# Sheet1.net
KiCad netlist of a schematic drawn in Altium Designer
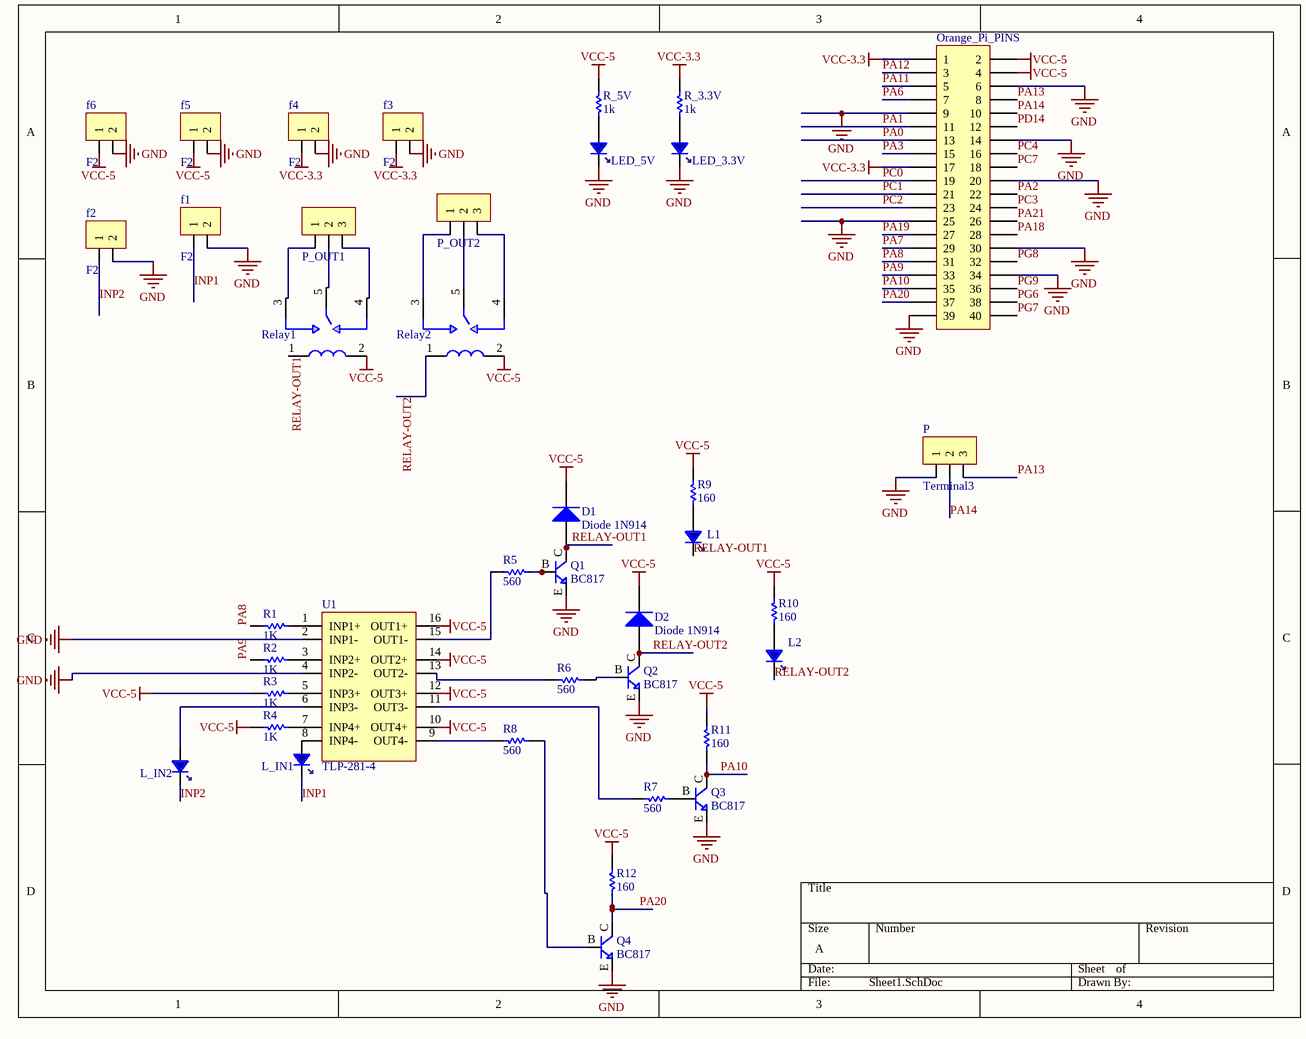
[diagram p0: Sheet1.SchDoc]

(export (version "E")
  (design (tool "Eeschema 10.0.6"))
  (components
    (comp (ref "D1")
      (value "Diode 1N914")
      (footprint "DO-35")
      (description "High Conductance Fast Diode")
      (fields (field (name "PUBLISHER") "Altium Limited"))
      (libsource (lib "Miscellaneous Devices") (part "Diode 1N914"))
    )
    (comp (ref "D2")
      (value "Diode 1N914")
      (footprint "DO-35")
      (description "High Conductance Fast Diode")
      (fields (field (name "PUBLISHER") "Altium Limited"))
      (libsource (lib "Miscellaneous Devices") (part "Diode 1N914"))
    )
    (comp (ref "f1")
      (value "F2")
      (footprint "Fonex(X2):PCBComponent_1")
      (libsource (lib "Fonex(X2)") (part "Component_1"))
    )
    (comp (ref "f2")
      (value "F2")
      (footprint "Fonex(X2):PCBComponent_1")
      (libsource (lib "Fonex(X2)") (part "Component_1"))
    )
    (comp (ref "f3")
      (value "F2")
      (footprint "Fonex(X2):PCBComponent_1")
      (libsource (lib "Fonex(X2)") (part "Component_1"))
    )
    (comp (ref "f4")
      (value "F2")
      (footprint "Fonex(X2):PCBComponent_1")
      (libsource (lib "Fonex(X2)") (part "Component_1"))
    )
    (comp (ref "f5")
      (value "F2")
      (footprint "Fonex(X2):PCBComponent_1")
      (libsource (lib "Fonex(X2)") (part "Component_1"))
    )
    (comp (ref "f6")
      (value "F2")
      (footprint "Fonex(X2):PCBComponent_1")
      (libsource (lib "Fonex(X2)") (part "Component_1"))
    )
    (comp (ref "L1")
      (value "LED_0805")
      (footprint "LED_0805")
      (libsource (lib "Main Board") (part "LED_0805"))
    )
    (comp (ref "L2")
      (value "LED_0805")
      (footprint "LED_0805")
      (libsource (lib "Main Board") (part "LED_0805"))
    )
    (comp (ref "LED_3.3V")
      (value "LED_0805")
      (footprint "LED_0805")
      (libsource (lib "Main Board") (part "LED_0805"))
    )
    (comp (ref "LED_5V")
      (value "LED_0805")
      (footprint "LED_0805")
      (libsource (lib "Main Board") (part "LED_0805"))
    )
    (comp (ref "L_IN1")
      (value "LED_0805")
      (footprint "LED_0805")
      (libsource (lib "Main Board") (part "LED_0805"))
    )
    (comp (ref "L_IN2")
      (value "LED_0805")
      (footprint "LED_0805")
      (libsource (lib "Main Board") (part "LED_0805"))
    )
    (comp (ref "Orange_Pi_PINS")
      (value "Header 20X2")
      (footprint "HDR2X20")
      (description "Header, 20-Pin, Dual row")
      (fields (field (name "PUBLISHER") "Altium Limited"))
      (libsource (lib "Miscellaneous Connectors") (part "Header 20X2"))
    )
    (comp (ref "P")
      (value "Terminal3")
      (footprint "TERMINAL-3")
      (libsource (lib "Lib_Interface") (part "Terminal-3"))
    )
    (comp (ref "P_OUT1")
      (value "Terminal3")
      (footprint "TERMINAL-3")
      (libsource (lib "Lib_Interface") (part "Terminal-3"))
    )
    (comp (ref "P_OUT2")
      (value "Terminal3")
      (footprint "TERMINAL-3")
      (libsource (lib "Lib_Interface") (part "Terminal-3"))
    )
    (comp (ref "Q1")
      (value "BC817")
      (footprint "PCBComponent_1 - duplicate2")
      (libsource (lib "Lib_Interface") (part "Transistor_SMD_NPN"))
    )
    (comp (ref "Q2")
      (value "BC817")
      (footprint "PCBComponent_1 - duplicate2")
      (libsource (lib "Lib_Interface") (part "Transistor_SMD_NPN"))
    )
    (comp (ref "Q3")
      (value "BC817")
      (footprint "PCBComponent_1 - duplicate2")
      (libsource (lib "Lib_Interface") (part "Transistor_SMD_NPN"))
    )
    (comp (ref "Q4")
      (value "BC817")
      (footprint "PCBComponent_1 - duplicate2")
      (libsource (lib "Lib_Interface") (part "Transistor_SMD_NPN"))
    )
    (comp (ref "R1")
      (value "1K")
      (footprint "ResS")
      (fields (field (name "Comment") "Res_0805"))
      (libsource (lib "Main Board") (part "Res_0805"))
    )
    (comp (ref "R2")
      (value "1K")
      (footprint "ResS")
      (fields (field (name "Comment") "Res_0805"))
      (libsource (lib "Main Board") (part "Res_0805"))
    )
    (comp (ref "R3")
      (value "1K")
      (footprint "ResS")
      (fields (field (name "Comment") "Res_0805"))
      (libsource (lib "Main Board") (part "Res_0805"))
    )
    (comp (ref "R4")
      (value "1K")
      (footprint "ResS")
      (fields (field (name "Comment") "Res_0805"))
      (libsource (lib "Main Board") (part "Res_0805"))
    )
    (comp (ref "R5")
      (value "560")
      (footprint "ResS")
      (fields (field (name "Comment") "Res_0805"))
      (libsource (lib "Main Board") (part "Res_0805"))
    )
    (comp (ref "R6")
      (value "560")
      (footprint "ResS")
      (fields (field (name "Comment") "Res_0805"))
      (libsource (lib "Main Board") (part "Res_0805"))
    )
    (comp (ref "R7")
      (value "560")
      (footprint "ResS")
      (fields (field (name "Comment") "Res_0805"))
      (libsource (lib "Main Board") (part "Res_0805"))
    )
    (comp (ref "R8")
      (value "560")
      (footprint "ResS")
      (fields (field (name "Comment") "Res_0805"))
      (libsource (lib "Main Board") (part "Res_0805"))
    )
    (comp (ref "R9")
      (value "160")
      (footprint "ResS")
      (fields (field (name "Comment") "Res_0805"))
      (libsource (lib "Main Board") (part "Res_0805"))
    )
    (comp (ref "R10")
      (value "160")
      (footprint "ResS")
      (fields (field (name "Comment") "Res_0805"))
      (libsource (lib "Main Board") (part "Res_0805"))
    )
    (comp (ref "R11")
      (value "160")
      (footprint "ResS")
      (fields (field (name "Comment") "Res_0805"))
      (libsource (lib "Main Board") (part "Res_0805"))
    )
    (comp (ref "R12")
      (value "160")
      (footprint "ResS")
      (fields (field (name "Comment") "Res_0805"))
      (libsource (lib "Main Board") (part "Res_0805"))
    )
    (comp (ref "Relay1")
      (value "JOC-3FF")
      (footprint "Interface-PCB-Lib:PCBComponent_1")
      (description "Relay")
      (libsource (lib "Lib_Interface") (part "Relay-5VDC"))
    )
    (comp (ref "Relay2")
      (value "JOC-3FF")
      (footprint "Interface-PCB-Lib:PCBComponent_1")
      (description "Relay")
      (libsource (lib "Lib_Interface") (part "Relay-5VDC"))
    )
    (comp (ref "R_3.3V")
      (value "1k")
      (footprint "ResS")
      (fields (field (name "Comment") "Res_0805"))
      (libsource (lib "Main Board") (part "Res_0805"))
    )
    (comp (ref "R_5V")
      (value "1k")
      (footprint "ResS")
      (fields (field (name "Comment") "Res_0805"))
      (libsource (lib "Main Board") (part "Res_0805"))
    )
    (comp (ref "U1")
      (value "TLP-281-4")
      (footprint "TLP281-4")
      (libsource (lib "Lib_Interface") (part "OPTO-TLP281-4"))
    )
  )
  (nets
    (net (code "1") (name "/INP1") (class "Default")
      (node (ref "L_IN1") (pin "2") (pinfunction "CATHODE_2") (pintype "passive"))
      (node (ref "f1") (pin "1") (pinfunction "1_1") (pintype "passive"))
    )
    (net (code "2") (name "/INP2") (class "Default")
      (node (ref "L_IN2") (pin "2") (pinfunction "CATHODE_2") (pintype "passive"))
      (node (ref "f2") (pin "1") (pinfunction "1_1") (pintype "passive"))
    )
    (net (code "3") (name "/PA0") (class "Default")
      (node (ref "Orange_Pi_PINS") (pin "13") (pinfunction "13_13") (pintype "passive"))
    )
    (net (code "4") (name "/PA1") (class "Default")
      (node (ref "Orange_Pi_PINS") (pin "11") (pinfunction "11_11") (pintype "passive"))
    )
    (net (code "5") (name "/PA2") (class "Default")
      (node (ref "Orange_Pi_PINS") (pin "22") (pinfunction "22_22") (pintype "passive"))
    )
    (net (code "6") (name "/PA3") (class "Default")
      (node (ref "Orange_Pi_PINS") (pin "15") (pinfunction "15_15") (pintype "passive"))
    )
    (net (code "7") (name "/PA6") (class "Default")
      (node (ref "Orange_Pi_PINS") (pin "7") (pinfunction "7_7") (pintype "passive"))
    )
    (net (code "8") (name "/PA7") (class "Default")
      (node (ref "Orange_Pi_PINS") (pin "29") (pinfunction "29_29") (pintype "passive"))
    )
    (net (code "9") (name "/PA8") (class "Default")
      (node (ref "Orange_Pi_PINS") (pin "31") (pinfunction "31_31") (pintype "passive"))
      (node (ref "R1") (pin "2") (pinfunction "2_2") (pintype "passive"))
    )
    (net (code "10") (name "/PA9") (class "Default")
      (node (ref "Orange_Pi_PINS") (pin "33") (pinfunction "33_33") (pintype "passive"))
      (node (ref "R2") (pin "1") (pinfunction "1_1") (pintype "passive"))
    )
    (net (code "11") (name "/PA10") (class "Default")
      (node (ref "Orange_Pi_PINS") (pin "35") (pinfunction "35_35") (pintype "passive"))
      (node (ref "Q3") (pin "C") (pinfunction "C_C") (pintype "passive"))
      (node (ref "R11") (pin "1") (pinfunction "1_1") (pintype "passive"))
    )
    (net (code "12") (name "/PA11") (class "Default")
      (node (ref "Orange_Pi_PINS") (pin "5") (pinfunction "5_5") (pintype "passive"))
    )
    (net (code "13") (name "/PA12") (class "Default")
      (node (ref "Orange_Pi_PINS") (pin "3") (pinfunction "3_3") (pintype "passive"))
    )
    (net (code "14") (name "/PA13") (class "Default")
      (node (ref "Orange_Pi_PINS") (pin "8") (pinfunction "8_8") (pintype "passive"))
      (node (ref "P") (pin "3") (pinfunction "3_3") (pintype "passive"))
    )
    (net (code "15") (name "/PA14") (class "Default")
      (node (ref "Orange_Pi_PINS") (pin "10") (pinfunction "10_10") (pintype "passive"))
      (node (ref "P") (pin "2") (pinfunction "2_2") (pintype "passive"))
    )
    (net (code "16") (name "/PA18") (class "Default")
      (node (ref "Orange_Pi_PINS") (pin "28") (pinfunction "28_28") (pintype "passive"))
    )
    (net (code "17") (name "/PA19") (class "Default")
      (node (ref "Orange_Pi_PINS") (pin "27") (pinfunction "27_27") (pintype "passive"))
    )
    (net (code "18") (name "/PA20") (class "Default")
      (node (ref "Orange_Pi_PINS") (pin "37") (pinfunction "37_37") (pintype "passive"))
      (node (ref "Q4") (pin "C") (pinfunction "C_C") (pintype "passive"))
      (node (ref "R12") (pin "1") (pinfunction "1_1") (pintype "passive"))
    )
    (net (code "19") (name "/PA21") (class "Default")
      (node (ref "Orange_Pi_PINS") (pin "26") (pinfunction "26_26") (pintype "passive"))
    )
    (net (code "20") (name "/PC0") (class "Default")
      (node (ref "Orange_Pi_PINS") (pin "19") (pinfunction "19_19") (pintype "passive"))
    )
    (net (code "21") (name "/PC1") (class "Default")
      (node (ref "Orange_Pi_PINS") (pin "21") (pinfunction "21_21") (pintype "passive"))
    )
    (net (code "22") (name "/PC2") (class "Default")
      (node (ref "Orange_Pi_PINS") (pin "23") (pinfunction "23_23") (pintype "passive"))
    )
    (net (code "23") (name "/PC3") (class "Default")
      (node (ref "Orange_Pi_PINS") (pin "24") (pinfunction "24_24") (pintype "passive"))
    )
    (net (code "24") (name "/PC4") (class "Default")
      (node (ref "Orange_Pi_PINS") (pin "16") (pinfunction "16_16") (pintype "passive"))
    )
    (net (code "25") (name "/PC7") (class "Default")
      (node (ref "Orange_Pi_PINS") (pin "18") (pinfunction "18_18") (pintype "passive"))
    )
    (net (code "26") (name "/PD14") (class "Default")
      (node (ref "Orange_Pi_PINS") (pin "12") (pinfunction "12_12") (pintype "passive"))
    )
    (net (code "27") (name "/PG6") (class "Default")
      (node (ref "Orange_Pi_PINS") (pin "38") (pinfunction "38_38") (pintype "passive"))
    )
    (net (code "28") (name "/PG7") (class "Default")
      (node (ref "Orange_Pi_PINS") (pin "40") (pinfunction "40_40") (pintype "passive"))
    )
    (net (code "29") (name "/PG8") (class "Default")
      (node (ref "Orange_Pi_PINS") (pin "32") (pinfunction "32_32") (pintype "passive"))
    )
    (net (code "30") (name "/PG9") (class "Default")
      (node (ref "Orange_Pi_PINS") (pin "36") (pinfunction "36_36") (pintype "passive"))
    )
    (net (code "31") (name "/RELAY-OUT1") (class "Default")
      (node (ref "D1") (pin "1") (pinfunction "A_1") (pintype "passive"))
      (node (ref "L1") (pin "2") (pinfunction "CATHODE_2") (pintype "passive"))
      (node (ref "Q1") (pin "C") (pinfunction "C_C") (pintype "passive"))
      (node (ref "Relay1") (pin "1") (pinfunction "1_1") (pintype "passive"))
    )
    (net (code "32") (name "/RELAY-OUT2") (class "Default")
      (node (ref "D2") (pin "1") (pinfunction "A_1") (pintype "passive"))
      (node (ref "L2") (pin "2") (pinfunction "CATHODE_2") (pintype "passive"))
      (node (ref "Q2") (pin "C") (pinfunction "C_C") (pintype "passive"))
      (node (ref "Relay2") (pin "1") (pinfunction "1_1") (pintype "passive"))
    )
    (net (code "33") (name "GND") (class "Default")
      (node (ref "LED_3.3V") (pin "2") (pinfunction "CATHODE_2") (pintype "passive"))
      (node (ref "LED_5V") (pin "2") (pinfunction "CATHODE_2") (pintype "passive"))
      (node (ref "Orange_Pi_PINS") (pin "14") (pinfunction "14_14") (pintype "passive"))
      (node (ref "Orange_Pi_PINS") (pin "20") (pinfunction "20_20") (pintype "passive"))
      (node (ref "Orange_Pi_PINS") (pin "25") (pinfunction "25_25") (pintype "passive"))
      (node (ref "Orange_Pi_PINS") (pin "30") (pinfunction "30_30") (pintype "passive"))
      (node (ref "Orange_Pi_PINS") (pin "34") (pinfunction "34_34") (pintype "passive"))
      (node (ref "Orange_Pi_PINS") (pin "39") (pinfunction "39_39") (pintype "passive"))
      (node (ref "Orange_Pi_PINS") (pin "6") (pinfunction "6_6") (pintype "passive"))
      (node (ref "Orange_Pi_PINS") (pin "9") (pinfunction "9_9") (pintype "passive"))
      (node (ref "P") (pin "1") (pinfunction "1_1") (pintype "passive"))
      (node (ref "Q1") (pin "E") (pinfunction "E_E") (pintype "passive"))
      (node (ref "Q2") (pin "E") (pinfunction "E_E") (pintype "passive"))
      (node (ref "Q3") (pin "E") (pinfunction "E_E") (pintype "passive"))
      (node (ref "Q4") (pin "E") (pinfunction "E_E") (pintype "passive"))
      (node (ref "U1") (pin "2") (pinfunction "INP1-_2") (pintype "passive"))
      (node (ref "U1") (pin "4") (pinfunction "INP2-_4") (pintype "passive"))
      (node (ref "f1") (pin "2") (pinfunction "2_2") (pintype "passive"))
      (node (ref "f2") (pin "2") (pinfunction "2_2") (pintype "passive"))
      (node (ref "f3") (pin "2") (pinfunction "2_2") (pintype "passive"))
      (node (ref "f4") (pin "2") (pinfunction "2_2") (pintype "passive"))
      (node (ref "f5") (pin "2") (pinfunction "2_2") (pintype "passive"))
      (node (ref "f6") (pin "2") (pinfunction "2_2") (pintype "passive"))
    )
    (net (code "34") (name "Net-(L1-ANODE)") (class "Default")
      (node (ref "L1") (pin "1") (pinfunction "ANODE_1") (pintype "passive"))
      (node (ref "R9") (pin "1") (pinfunction "1_1") (pintype "passive"))
    )
    (net (code "35") (name "Net-(L2-ANODE)") (class "Default")
      (node (ref "L2") (pin "1") (pinfunction "ANODE_1") (pintype "passive"))
      (node (ref "R10") (pin "1") (pinfunction "1_1") (pintype "passive"))
    )
    (net (code "36") (name "Net-(LED_3.3V-ANODE)") (class "Default")
      (node (ref "LED_3.3V") (pin "1") (pinfunction "ANODE_1") (pintype "passive"))
      (node (ref "R_3.3V") (pin "2") (pinfunction "2_2") (pintype "passive"))
    )
    (net (code "37") (name "Net-(LED_5V-ANODE)") (class "Default")
      (node (ref "LED_5V") (pin "1") (pinfunction "ANODE_1") (pintype "passive"))
      (node (ref "R_5V") (pin "1") (pinfunction "1_1") (pintype "passive"))
    )
    (net (code "38") (name "Net-(L_IN1-ANODE)") (class "Default")
      (node (ref "L_IN1") (pin "1") (pinfunction "ANODE_1") (pintype "passive"))
      (node (ref "U1") (pin "8") (pinfunction "INP4-_8") (pintype "passive"))
    )
    (net (code "39") (name "Net-(L_IN2-ANODE)") (class "Default")
      (node (ref "L_IN2") (pin "1") (pinfunction "ANODE_1") (pintype "passive"))
      (node (ref "U1") (pin "6") (pinfunction "INP3-_6") (pintype "passive"))
    )
    (net (code "40") (name "Net-(P_OUT1-Pad1)") (class "Default")
      (node (ref "P_OUT1") (pin "1") (pinfunction "1_1") (pintype "passive"))
      (node (ref "Relay1") (pin "3") (pinfunction "3_3") (pintype "passive"))
    )
    (net (code "41") (name "Net-(P_OUT1-Pad2)") (class "Default")
      (node (ref "P_OUT1") (pin "2") (pinfunction "2_2") (pintype "passive"))
      (node (ref "Relay1") (pin "5") (pinfunction "5_5") (pintype "passive"))
    )
    (net (code "42") (name "Net-(P_OUT1-Pad3)") (class "Default")
      (node (ref "P_OUT1") (pin "3") (pinfunction "3_3") (pintype "passive"))
      (node (ref "Relay1") (pin "4") (pinfunction "4_4") (pintype "passive"))
    )
    (net (code "43") (name "Net-(P_OUT2-Pad1)") (class "Default")
      (node (ref "P_OUT2") (pin "1") (pinfunction "1_1") (pintype "passive"))
      (node (ref "Relay2") (pin "3") (pinfunction "3_3") (pintype "passive"))
    )
    (net (code "44") (name "Net-(P_OUT2-Pad2)") (class "Default")
      (node (ref "P_OUT2") (pin "2") (pinfunction "2_2") (pintype "passive"))
      (node (ref "Relay2") (pin "5") (pinfunction "5_5") (pintype "passive"))
    )
    (net (code "45") (name "Net-(P_OUT2-Pad3)") (class "Default")
      (node (ref "P_OUT2") (pin "3") (pinfunction "3_3") (pintype "passive"))
      (node (ref "Relay2") (pin "4") (pinfunction "4_4") (pintype "passive"))
    )
    (net (code "46") (name "Net-(Q1-PadB)") (class "Default")
      (node (ref "Q1") (pin "B") (pinfunction "B_B") (pintype "passive"))
      (node (ref "R5") (pin "2") (pinfunction "2_2") (pintype "passive"))
    )
    (net (code "47") (name "Net-(Q2-PadB)") (class "Default")
      (node (ref "Q2") (pin "B") (pinfunction "B_B") (pintype "passive"))
      (node (ref "R6") (pin "2") (pinfunction "2_2") (pintype "passive"))
    )
    (net (code "48") (name "Net-(Q3-PadB)") (class "Default")
      (node (ref "Q3") (pin "B") (pinfunction "B_B") (pintype "passive"))
      (node (ref "R7") (pin "2") (pinfunction "2_2") (pintype "passive"))
    )
    (net (code "49") (name "Net-(Q4-PadB)") (class "Default")
      (node (ref "Q4") (pin "B") (pinfunction "B_B") (pintype "passive"))
      (node (ref "R8") (pin "2") (pinfunction "2_2") (pintype "passive"))
    )
    (net (code "50") (name "Net-(U1-INP1+)") (class "Default")
      (node (ref "R1") (pin "1") (pinfunction "1_1") (pintype "passive"))
      (node (ref "U1") (pin "1") (pinfunction "INP1+_1") (pintype "passive"))
    )
    (net (code "51") (name "Net-(U1-INP2+)") (class "Default")
      (node (ref "R2") (pin "2") (pinfunction "2_2") (pintype "passive"))
      (node (ref "U1") (pin "3") (pinfunction "INP2+_3") (pintype "passive"))
    )
    (net (code "52") (name "Net-(U1-INP3+)") (class "Default")
      (node (ref "R3") (pin "2") (pinfunction "2_2") (pintype "passive"))
      (node (ref "U1") (pin "5") (pinfunction "INP3+_5") (pintype "passive"))
    )
    (net (code "53") (name "Net-(U1-INP4+)") (class "Default")
      (node (ref "R4") (pin "2") (pinfunction "2_2") (pintype "passive"))
      (node (ref "U1") (pin "7") (pinfunction "INP4+_7") (pintype "passive"))
    )
    (net (code "54") (name "Net-(U1-OUT1-)") (class "Default")
      (node (ref "R5") (pin "1") (pinfunction "1_1") (pintype "passive"))
      (node (ref "U1") (pin "15") (pinfunction "OUT1-_15") (pintype "passive"))
    )
    (net (code "55") (name "Net-(U1-OUT2-)") (class "Default")
      (node (ref "R6") (pin "1") (pinfunction "1_1") (pintype "passive"))
      (node (ref "U1") (pin "13") (pinfunction "OUT2-_13") (pintype "passive"))
    )
    (net (code "56") (name "Net-(U1-OUT3-)") (class "Default")
      (node (ref "R7") (pin "1") (pinfunction "1_1") (pintype "passive"))
      (node (ref "U1") (pin "11") (pinfunction "OUT3-_11") (pintype "passive"))
    )
    (net (code "57") (name "Net-(U1-OUT4-)") (class "Default")
      (node (ref "R8") (pin "1") (pinfunction "1_1") (pintype "passive"))
      (node (ref "U1") (pin "9") (pinfunction "OUT4-_9") (pintype "passive"))
    )
    (net (code "58") (name "VCC-3.3") (class "Default")
      (node (ref "Orange_Pi_PINS") (pin "1") (pinfunction "1_1") (pintype "passive"))
      (node (ref "Orange_Pi_PINS") (pin "17") (pinfunction "17_17") (pintype "passive"))
      (node (ref "R_3.3V") (pin "1") (pinfunction "1_1") (pintype "passive"))
      (node (ref "f3") (pin "1") (pinfunction "1_1") (pintype "passive"))
      (node (ref "f4") (pin "1") (pinfunction "1_1") (pintype "passive"))
    )
    (net (code "59") (name "VCC-5") (class "Default")
      (node (ref "D1") (pin "2") (pinfunction "K_2") (pintype "passive"))
      (node (ref "D2") (pin "2") (pinfunction "K_2") (pintype "passive"))
      (node (ref "Orange_Pi_PINS") (pin "2") (pinfunction "2_2") (pintype "passive"))
      (node (ref "Orange_Pi_PINS") (pin "4") (pinfunction "4_4") (pintype "passive"))
      (node (ref "R10") (pin "2") (pinfunction "2_2") (pintype "passive"))
      (node (ref "R11") (pin "2") (pinfunction "2_2") (pintype "passive"))
      (node (ref "R12") (pin "2") (pinfunction "2_2") (pintype "passive"))
      (node (ref "R3") (pin "1") (pinfunction "1_1") (pintype "passive"))
      (node (ref "R4") (pin "1") (pinfunction "1_1") (pintype "passive"))
      (node (ref "R9") (pin "2") (pinfunction "2_2") (pintype "passive"))
      (node (ref "R_5V") (pin "2") (pinfunction "2_2") (pintype "passive"))
      (node (ref "Relay1") (pin "2") (pinfunction "2_2") (pintype "passive"))
      (node (ref "Relay2") (pin "2") (pinfunction "2_2") (pintype "passive"))
      (node (ref "U1") (pin "10") (pinfunction "OUT4+_10") (pintype "passive"))
      (node (ref "U1") (pin "12") (pinfunction "OUT3+_12") (pintype "passive"))
      (node (ref "U1") (pin "14") (pinfunction "OUT2+_14") (pintype "passive"))
      (node (ref "U1") (pin "16") (pinfunction "OUT1+_16") (pintype "passive"))
      (node (ref "f5") (pin "1") (pinfunction "1_1") (pintype "passive"))
      (node (ref "f6") (pin "1") (pinfunction "1_1") (pintype "passive"))
    )
  )
)
